# oLoRa-part-motherboard.net
KiCad netlist of a schematic drawn in EasyEDA
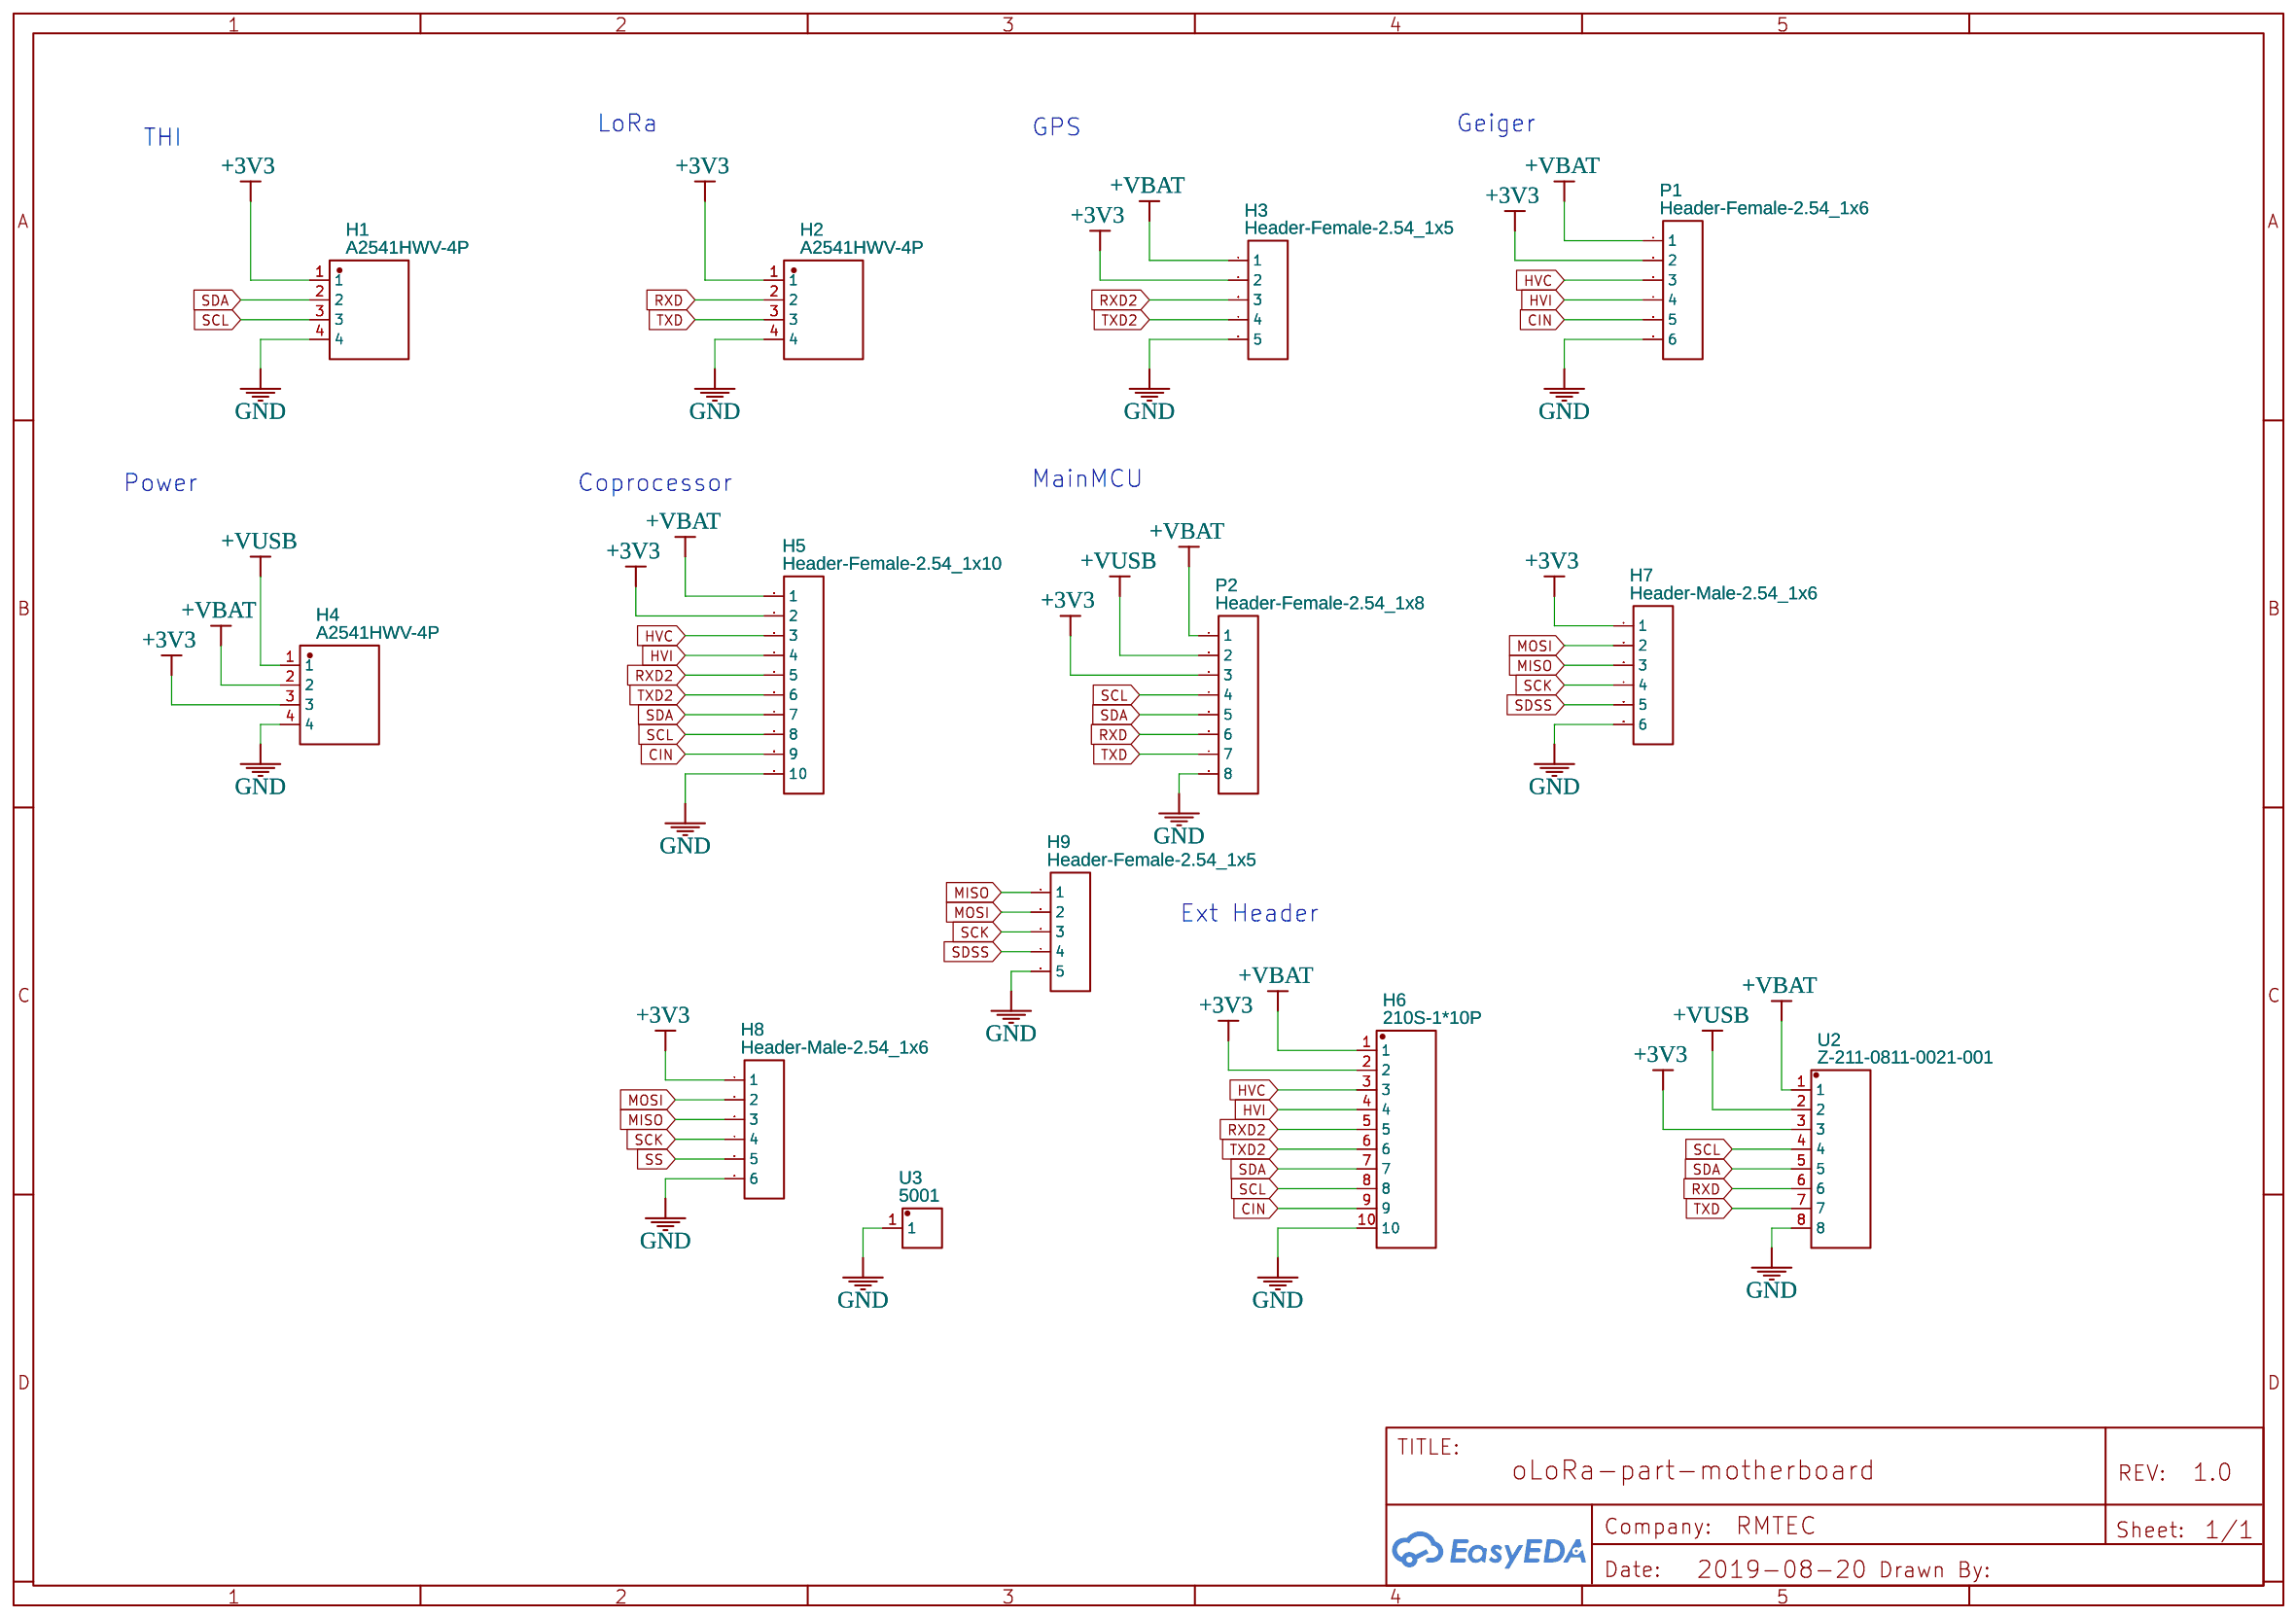
[diagram p0: schematic sheet]

(export (version "E")
  (design (tool "Eeschema 10.0.6"))
  (components
    (comp (ref "H1")
      (value "A2541HWV-4P")
      (fields (field (name "BOM_Supplier Part") "C225501"))
      (libsource (lib "") (part "Unknown_175_150"))
    )
    (comp (ref "H2")
      (value "A2541HWV-4P")
      (fields (field (name "BOM_Supplier Part") "C225501"))
      (libsource (lib "") (part "Unknown_405_150"))
    )
    (comp (ref "H3")
      (value "Header-Female-2.54_1x5")
      (fields
        (field (name "BOM_Manufacturer Part") "2.54mm 1*5p Female header")
        (field (name "BOM_Supplier Part") "C50950")
      )
      (libsource (lib "") (part "Unknown_630_145"))
    )
    (comp (ref "H4")
      (value "A2541HWV-4P")
      (fields (field (name "BOM_Supplier Part") "C225501"))
      (libsource (lib "") (part "Unknown_160_345"))
    )
    (comp (ref "H5")
      (value "Header-Female-2.54_1x10")
      (fields
        (field (name "BOM_Manufacturer Part") "2.54mm 1*10P Straight Female header Gold-plated")
        (field (name "BOM_Supplier Part") "C35445")
      )
      (libsource (lib "") (part "Unknown_390_345"))
    )
    (comp (ref "H6")
      (value "210S-1*10P")
      (fields
        (field (name "BOM_Manufacturer Part") "210S-1*10P L=11.6MMGold-plated black")
        (field (name "BOM_Supplier Part") "C124372")
      )
      (libsource (lib "") (part "Unknown_700_570"))
    )
    (comp (ref "H7")
      (value "Header-Male-2.54_1x6")
      (fields (field (name "BOM_Supplier Part") "C37208"))
      (libsource (lib "") (part "Unknown_825_335"))
    )
    (comp (ref "H8")
      (value "Header-Male-2.54_1x6")
      (fields (field (name "BOM_Supplier Part") "C37208"))
      (libsource (lib "") (part "Unknown_375_565"))
    )
    (comp (ref "H9")
      (value "Header-Female-2.54_1x5")
      (fields
        (field (name "BOM_Manufacturer Part") "2.54mm 1*5p Female header")
        (field (name "BOM_Supplier Part") "C50950")
      )
      (libsource (lib "") (part "Unknown_530_465"))
    )
    (comp (ref "P1")
      (value "Header-Female-2.54_1x6")
      (fields
        (field (name "BOM_Manufacturer Part") "Female header 1*6p")
        (field (name "BOM_Supplier Part") "C40877")
      )
      (libsource (lib "") (part "Unknown_840_140"))
    )
    (comp (ref "P2")
      (value "Header-Female-2.54_1x8")
      (fields
        (field (name "BOM_Manufacturer Part") "Female headerHDR1X8-2.54")
        (field (name "BOM_Supplier Part") "C27438")
      )
      (libsource (lib "") (part "Unknown_615_350"))
    )
    (comp (ref "U2")
      (value "Z-211-0811-0021-001")
      (fields (field (name "BOM_Supplier Part") "C190820"))
      (libsource (lib "") (part "Unknown_920_580"))
    )
    (comp (ref "U3")
      (value "5001")
      (fields (field (name "BOM_Supplier Part") "C238122"))
      (libsource (lib "") (part "Unknown_460_615"))
    )
  )
  (nets
    (net (code "1") (name "+3V3") (class "Default")
      (node (ref "H1") (pin "1") (pinfunction "1_1") (pintype "unspecified"))
      (node (ref "H2") (pin "1") (pinfunction "1_1") (pintype "unspecified"))
      (node (ref "H3") (pin "2") (pinfunction "2_2") (pintype "input"))
      (node (ref "H4") (pin "3") (pinfunction "3_3") (pintype "unspecified"))
      (node (ref "H5") (pin "2") (pinfunction "2_2") (pintype "input"))
      (node (ref "H6") (pin "2") (pinfunction "2_2") (pintype "unspecified"))
      (node (ref "H7") (pin "1") (pinfunction "1_1") (pintype "input"))
      (node (ref "H8") (pin "1") (pinfunction "1_1") (pintype "input"))
      (node (ref "P1") (pin "2") (pinfunction "2_2") (pintype "input"))
      (node (ref "P2") (pin "3") (pinfunction "3_3") (pintype "input"))
      (node (ref "U2") (pin "3") (pinfunction "3_3") (pintype "unspecified"))
    )
    (net (code "2") (name "+VBAT") (class "Default")
      (node (ref "H3") (pin "1") (pinfunction "1_1") (pintype "input"))
      (node (ref "H4") (pin "2") (pinfunction "2_2") (pintype "unspecified"))
      (node (ref "H5") (pin "1") (pinfunction "1_1") (pintype "input"))
      (node (ref "H6") (pin "1") (pinfunction "1_1") (pintype "unspecified"))
      (node (ref "P1") (pin "1") (pinfunction "1_1") (pintype "input"))
      (node (ref "P2") (pin "1") (pinfunction "1_1") (pintype "input"))
      (node (ref "U2") (pin "1") (pinfunction "1_1") (pintype "unspecified"))
    )
    (net (code "3") (name "+VUSB") (class "Default")
      (node (ref "H4") (pin "1") (pinfunction "1_1") (pintype "unspecified"))
      (node (ref "P2") (pin "2") (pinfunction "2_2") (pintype "input"))
      (node (ref "U2") (pin "2") (pinfunction "2_2") (pintype "unspecified"))
    )
    (net (code "4") (name "CIN") (class "Default")
      (node (ref "H5") (pin "9") (pinfunction "9_9") (pintype "input"))
      (node (ref "H6") (pin "9") (pinfunction "9_9") (pintype "unspecified"))
      (node (ref "P1") (pin "5") (pinfunction "5_5") (pintype "input"))
    )
    (net (code "5") (name "GND") (class "Default")
      (node (ref "H1") (pin "4") (pinfunction "4_4") (pintype "unspecified"))
      (node (ref "H2") (pin "4") (pinfunction "4_4") (pintype "unspecified"))
      (node (ref "H3") (pin "5") (pinfunction "5_5") (pintype "input"))
      (node (ref "H4") (pin "4") (pinfunction "4_4") (pintype "unspecified"))
      (node (ref "H5") (pin "10") (pinfunction "10_10") (pintype "input"))
      (node (ref "H6") (pin "10") (pinfunction "10_10") (pintype "unspecified"))
      (node (ref "H7") (pin "6") (pinfunction "6_6") (pintype "input"))
      (node (ref "H8") (pin "6") (pinfunction "6_6") (pintype "input"))
      (node (ref "H9") (pin "5") (pinfunction "5_5") (pintype "input"))
      (node (ref "P1") (pin "6") (pinfunction "6_6") (pintype "input"))
      (node (ref "P2") (pin "8") (pinfunction "8_8") (pintype "input"))
      (node (ref "U2") (pin "8") (pinfunction "8_8") (pintype "unspecified"))
      (node (ref "U3") (pin "1") (pinfunction "1_1") (pintype "unspecified"))
    )
    (net (code "6") (name "HVC") (class "Default")
      (node (ref "H5") (pin "3") (pinfunction "3_3") (pintype "input"))
      (node (ref "H6") (pin "3") (pinfunction "3_3") (pintype "unspecified"))
      (node (ref "P1") (pin "3") (pinfunction "3_3") (pintype "input"))
    )
    (net (code "7") (name "HVI") (class "Default")
      (node (ref "H5") (pin "4") (pinfunction "4_4") (pintype "input"))
      (node (ref "H6") (pin "4") (pinfunction "4_4") (pintype "unspecified"))
      (node (ref "P1") (pin "4") (pinfunction "4_4") (pintype "input"))
    )
    (net (code "8") (name "MISO") (class "Default")
      (node (ref "H7") (pin "3") (pinfunction "3_3") (pintype "input"))
      (node (ref "H8") (pin "3") (pinfunction "3_3") (pintype "input"))
      (node (ref "H9") (pin "1") (pinfunction "1_1") (pintype "input"))
    )
    (net (code "9") (name "MOSI") (class "Default")
      (node (ref "H7") (pin "2") (pinfunction "2_2") (pintype "input"))
      (node (ref "H8") (pin "2") (pinfunction "2_2") (pintype "input"))
      (node (ref "H9") (pin "2") (pinfunction "2_2") (pintype "input"))
    )
    (net (code "10") (name "RXD") (class "Default")
      (node (ref "H2") (pin "2") (pinfunction "2_2") (pintype "unspecified"))
      (node (ref "P2") (pin "6") (pinfunction "6_6") (pintype "input"))
      (node (ref "U2") (pin "6") (pinfunction "6_6") (pintype "unspecified"))
    )
    (net (code "11") (name "RXD2") (class "Default")
      (node (ref "H3") (pin "3") (pinfunction "3_3") (pintype "input"))
      (node (ref "H5") (pin "5") (pinfunction "5_5") (pintype "input"))
      (node (ref "H6") (pin "5") (pinfunction "5_5") (pintype "unspecified"))
    )
    (net (code "12") (name "SCK") (class "Default")
      (node (ref "H7") (pin "4") (pinfunction "4_4") (pintype "input"))
      (node (ref "H8") (pin "4") (pinfunction "4_4") (pintype "input"))
      (node (ref "H9") (pin "3") (pinfunction "3_3") (pintype "input"))
    )
    (net (code "13") (name "SCL") (class "Default")
      (node (ref "H1") (pin "3") (pinfunction "3_3") (pintype "unspecified"))
      (node (ref "H5") (pin "8") (pinfunction "8_8") (pintype "input"))
      (node (ref "H6") (pin "8") (pinfunction "8_8") (pintype "unspecified"))
      (node (ref "P2") (pin "4") (pinfunction "4_4") (pintype "input"))
      (node (ref "U2") (pin "4") (pinfunction "4_4") (pintype "unspecified"))
    )
    (net (code "14") (name "SDA") (class "Default")
      (node (ref "H1") (pin "2") (pinfunction "2_2") (pintype "unspecified"))
      (node (ref "H5") (pin "7") (pinfunction "7_7") (pintype "input"))
      (node (ref "H6") (pin "7") (pinfunction "7_7") (pintype "unspecified"))
      (node (ref "P2") (pin "5") (pinfunction "5_5") (pintype "input"))
      (node (ref "U2") (pin "5") (pinfunction "5_5") (pintype "unspecified"))
    )
    (net (code "15") (name "SDSS") (class "Default")
      (node (ref "H7") (pin "5") (pinfunction "5_5") (pintype "input"))
      (node (ref "H9") (pin "4") (pinfunction "4_4") (pintype "input"))
    )
    (net (code "16") (name "SS") (class "Default")
      (node (ref "H8") (pin "5") (pinfunction "5_5") (pintype "input"))
    )
    (net (code "17") (name "TXD") (class "Default")
      (node (ref "H2") (pin "3") (pinfunction "3_3") (pintype "unspecified"))
      (node (ref "P2") (pin "7") (pinfunction "7_7") (pintype "input"))
      (node (ref "U2") (pin "7") (pinfunction "7_7") (pintype "unspecified"))
    )
    (net (code "18") (name "TXD2") (class "Default")
      (node (ref "H3") (pin "4") (pinfunction "4_4") (pintype "input"))
      (node (ref "H5") (pin "6") (pinfunction "6_6") (pintype "input"))
      (node (ref "H6") (pin "6") (pinfunction "6_6") (pintype "unspecified"))
    )
  )
)
